# pqc-rev3.net
KiCad netlist of a schematic drawn in EAGLE
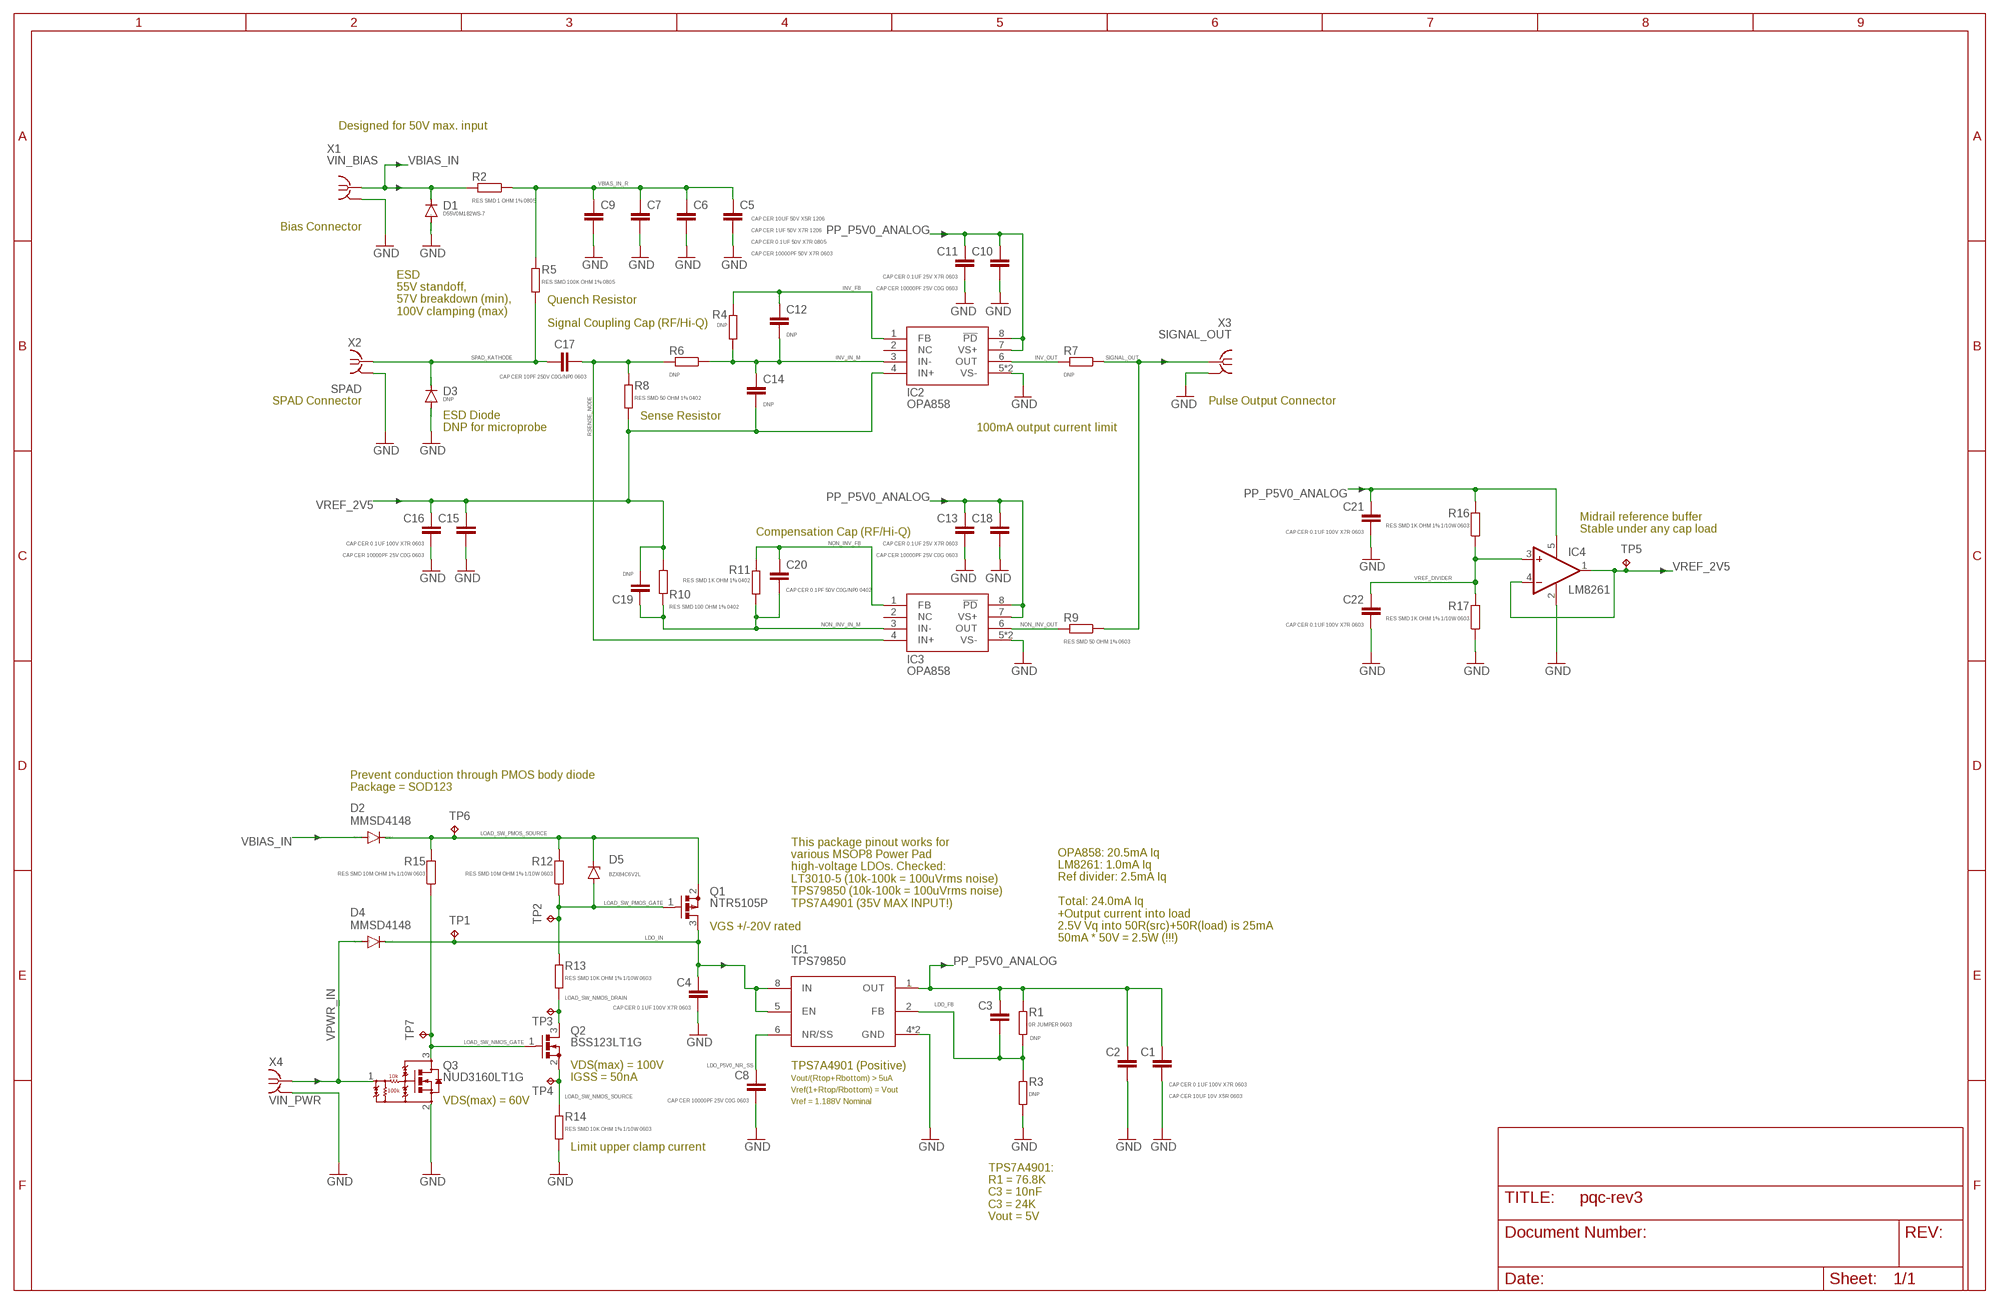
[diagram p0: schematic, sheet 1]

(export (version "E")
  (design (tool "Eeschema 10.0.6"))
  (components
    (comp (ref "C1")
      (value "CAP CER 10UF 10V X5R 0603")
      (footprint "eagle-import:C0603")
      (libsource (lib "eagle-import") (part "rcl-modified-footprints_C-EUC0603"))
    )
    (comp (ref "C2")
      (value "CAP CER 0.1UF 100V X7R 0603")
      (footprint "eagle-import:C0603")
      (libsource (lib "eagle-import") (part "rcl-modified-footprints_C-EUC0603"))
    )
    (comp (ref "C3")
      (value "DNP")
      (footprint "eagle-import:C0603")
      (libsource (lib "eagle-import") (part "rcl-modified-footprints_C-EUC0603"))
    )
    (comp (ref "C4")
      (value "CAP CER 0.1UF 100V X7R 0603")
      (footprint "eagle-import:C0603")
      (libsource (lib "eagle-import") (part "rcl-modified-footprints_C-EUC0603"))
    )
    (comp (ref "C5")
      (value "CAP CER 10UF 50V X5R 1206")
      (footprint "eagle-import:C1206")
      (libsource (lib "eagle-import") (part "C-EUC1206"))
    )
    (comp (ref "C6")
      (value "CAP CER 1UF 50V X7R 1206")
      (footprint "eagle-import:C1206")
      (libsource (lib "eagle-import") (part "C-EUC1206"))
    )
    (comp (ref "C7")
      (value "CAP CER 0.1UF 50V X7R 0805")
      (footprint "eagle-import:C0805")
      (libsource (lib "eagle-import") (part "C-EUC0805"))
    )
    (comp (ref "C8")
      (value "CAP CER 10000PF 25V C0G 0603")
      (footprint "eagle-import:C0603")
      (libsource (lib "eagle-import") (part "rcl-modified-footprints_C-EUC0603"))
    )
    (comp (ref "C9")
      (value "CAP CER 10000PF 50V X7R 0603")
      (footprint "eagle-import:C0603")
      (libsource (lib "eagle-import") (part "rcl-modified-footprints_C-EUC0603"))
    )
    (comp (ref "C10")
      (value "CAP CER 10000PF 25V C0G 0603")
      (footprint "eagle-import:C0603")
      (libsource (lib "eagle-import") (part "rcl-modified-footprints_C-EUC0603"))
    )
    (comp (ref "C11")
      (value "CAP CER 0.1UF 25V X7R 0603")
      (footprint "eagle-import:C0603")
      (libsource (lib "eagle-import") (part "rcl-modified-footprints_C-EUC0603"))
    )
    (comp (ref "C12")
      (value "DNP")
      (footprint "eagle-import:C0402")
      (libsource (lib "eagle-import") (part "rcl-modified-footprints_C-EUC0402"))
    )
    (comp (ref "C13")
      (value "CAP CER 0.1UF 25V X7R 0603")
      (footprint "eagle-import:C0603")
      (libsource (lib "eagle-import") (part "rcl-modified-footprints_C-EUC0603"))
    )
    (comp (ref "C14")
      (value "DNP")
      (footprint "eagle-import:C0402")
      (libsource (lib "eagle-import") (part "rcl-modified-footprints_C-EUC0402"))
    )
    (comp (ref "C15")
      (value "CAP CER 10000PF 25V C0G 0603")
      (footprint "eagle-import:C0603")
      (libsource (lib "eagle-import") (part "rcl-modified-footprints_C-EUC0603"))
    )
    (comp (ref "C16")
      (value "CAP CER 0.1UF 100V X7R 0603")
      (footprint "eagle-import:C0603")
      (libsource (lib "eagle-import") (part "rcl-modified-footprints_C-EUC0603"))
    )
    (comp (ref "C17")
      (value "CAP CER 10PF 250V C0G/NP0 0603")
      (footprint "eagle-import:C0603")
      (libsource (lib "eagle-import") (part "rcl-modified-footprints_C-EUC0603"))
    )
    (comp (ref "C18")
      (value "CAP CER 10000PF 25V C0G 0603")
      (footprint "eagle-import:C0603")
      (libsource (lib "eagle-import") (part "rcl-modified-footprints_C-EUC0603"))
    )
    (comp (ref "C19")
      (value "DNP")
      (footprint "eagle-import:C0402")
      (libsource (lib "eagle-import") (part "rcl-modified-footprints_C-EUC0402"))
    )
    (comp (ref "C20")
      (value "CAP CER 0.1PF 50V C0G/NP0 0402")
      (footprint "eagle-import:C0402")
      (libsource (lib "eagle-import") (part "rcl-modified-footprints_C-EUC0402"))
    )
    (comp (ref "C21")
      (value "CAP CER 0.1UF 100V X7R 0603")
      (footprint "eagle-import:C0603")
      (libsource (lib "eagle-import") (part "rcl-modified-footprints_C-EUC0603"))
    )
    (comp (ref "C22")
      (value "CAP CER 0.1UF 100V X7R 0603")
      (footprint "eagle-import:C0603")
      (libsource (lib "eagle-import") (part "rcl-modified-footprints_C-EUC0603"))
    )
    (comp (ref "D1")
      (value "D55V0M1B2WS-7")
      (footprint "eagle-import:SOD323-W")
      (libsource (lib "eagle-import") (part "DIODE-SOD323-W"))
    )
    (comp (ref "D2")
      (value "MMSD4148")
      (footprint "eagle-import:SOD123")
      (libsource (lib "eagle-import") (part "DIODE-SOD123"))
    )
    (comp (ref "D3")
      (value "DNP")
      (footprint "eagle-import:SOD323-W")
      (libsource (lib "eagle-import") (part "DIODE-SOD323-W"))
    )
    (comp (ref "D4")
      (value "MMSD4148")
      (footprint "eagle-import:SOD123")
      (libsource (lib "eagle-import") (part "DIODE-SOD123"))
    )
    (comp (ref "D5")
      (value "BZX84C6V2L")
      (footprint "eagle-import:SOT23")
      (libsource (lib "eagle-import") (part "ZENER-DIODESOT23"))
    )
    (comp (ref "IC1")
      (value "TPS79850")
      (footprint "eagle-import:MSOP-8_POWER_PAD")
      (libsource (lib "eagle-import") (part "TPS7A"))
    )
    (comp (ref "IC2")
      (value "OPA858")
      (footprint "eagle-import:WSON8")
      (libsource (lib "eagle-import") (part "OPA858"))
    )
    (comp (ref "IC3")
      (value "OPA858")
      (footprint "eagle-import:WSON8")
      (libsource (lib "eagle-import") (part "OPA858"))
    )
    (comp (ref "IC4")
      (value "LM8261")
      (footprint "eagle-import:SOT23-5")
      (libsource (lib "eagle-import") (part "LM8261"))
    )
    (comp (ref "Q1")
      (value "NTR5105P")
      (footprint "eagle-import:SOT23C")
      (libsource (lib "eagle-import") (part "PMOS_GENERIC_SOT23-3"))
    )
    (comp (ref "Q2")
      (value "BSS123LT1G")
      (footprint "eagle-import:SOT23C")
      (libsource (lib "eagle-import") (part "NMOS_GENERIC"))
    )
    (comp (ref "Q3")
      (value "NUD3160LT1G")
      (footprint "eagle-import:SOT23C")
      (libsource (lib "eagle-import") (part "NUD3160LT1G"))
    )
    (comp (ref "R1")
      (value "0R JUMPER 0603")
      (footprint "eagle-import:R0603")
      (libsource (lib "eagle-import") (part "R-EU_R0603"))
    )
    (comp (ref "R2")
      (value "RES SMD 1 OHM 1% 0805")
      (footprint "eagle-import:R0805")
      (libsource (lib "eagle-import") (part "rcl_334_R-EU_R0805"))
    )
    (comp (ref "R3")
      (value "DNP")
      (footprint "eagle-import:R0603")
      (libsource (lib "eagle-import") (part "R-EU_R0603"))
    )
    (comp (ref "R4")
      (value "DNP")
      (footprint "eagle-import:R0402")
      (libsource (lib "eagle-import") (part "R-EU_R0402"))
    )
    (comp (ref "R5")
      (value "RES SMD 100K OHM 1% 0805")
      (footprint "eagle-import:R0805")
      (libsource (lib "eagle-import") (part "rcl_334_R-EU_R0805"))
    )
    (comp (ref "R6")
      (value "DNP")
      (footprint "eagle-import:R0402")
      (libsource (lib "eagle-import") (part "R-EU_R0402"))
    )
    (comp (ref "R7")
      (value "DNP")
      (footprint "eagle-import:R0603")
      (libsource (lib "eagle-import") (part "R-EU_R0603"))
    )
    (comp (ref "R8")
      (value "RES SMD 50 OHM 1% 0402")
      (footprint "eagle-import:R0402")
      (libsource (lib "eagle-import") (part "R-EU_R0402"))
    )
    (comp (ref "R9")
      (value "RES SMD 50 OHM 1% 0603")
      (footprint "eagle-import:R0603")
      (libsource (lib "eagle-import") (part "R-EU_R0603"))
    )
    (comp (ref "R10")
      (value "RES SMD 100 OHM 1% 0402")
      (footprint "eagle-import:R0402")
      (libsource (lib "eagle-import") (part "R-EU_R0402"))
    )
    (comp (ref "R11")
      (value "RES SMD 1K OHM 1% 0402")
      (footprint "eagle-import:R0402")
      (libsource (lib "eagle-import") (part "R-EU_R0402"))
    )
    (comp (ref "R12")
      (value "RES SMD 10M OHM 1% 1/10W 0603")
      (footprint "eagle-import:R0603")
      (libsource (lib "eagle-import") (part "R-EU_R0603"))
    )
    (comp (ref "R13")
      (value "RES SMD 10K OHM 1% 1/10W 0603")
      (footprint "eagle-import:R0603")
      (libsource (lib "eagle-import") (part "R-EU_R0603"))
    )
    (comp (ref "R14")
      (value "RES SMD 10K OHM 1% 1/10W 0603")
      (footprint "eagle-import:R0603")
      (libsource (lib "eagle-import") (part "R-EU_R0603"))
    )
    (comp (ref "R15")
      (value "RES SMD 10M OHM 1% 1/10W 0603")
      (footprint "eagle-import:R0603")
      (libsource (lib "eagle-import") (part "R-EU_R0603"))
    )
    (comp (ref "R16")
      (value "RES SMD 1K OHM 1% 1/10W 0603")
      (footprint "eagle-import:R0603")
      (libsource (lib "eagle-import") (part "R-EU_R0603"))
    )
    (comp (ref "R17")
      (value "RES SMD 1K OHM 1% 1/10W 0603")
      (footprint "eagle-import:R0603")
      (libsource (lib "eagle-import") (part "R-EU_R0603"))
    )
    (comp (ref "TP1")
      (value "TPTP10R")
      (footprint "eagle-import:TP10R")
      (libsource (lib "eagle-import") (part "TPTP10R"))
    )
    (comp (ref "TP2")
      (value "TPTP10R")
      (footprint "eagle-import:TP10R")
      (libsource (lib "eagle-import") (part "TPTP10R"))
    )
    (comp (ref "TP3")
      (value "TPTP10R")
      (footprint "eagle-import:TP10R")
      (libsource (lib "eagle-import") (part "TPTP10R"))
    )
    (comp (ref "TP4")
      (value "TPTP10R")
      (footprint "eagle-import:TP10R")
      (libsource (lib "eagle-import") (part "TPTP10R"))
    )
    (comp (ref "TP5")
      (value "TPTP10R")
      (footprint "eagle-import:TP10R")
      (libsource (lib "eagle-import") (part "TPTP10R"))
    )
    (comp (ref "TP6")
      (value "TPTP10R")
      (footprint "eagle-import:TP10R")
      (libsource (lib "eagle-import") (part "TPTP10R"))
    )
    (comp (ref "TP7")
      (value "TPB1,27")
      (footprint "eagle-import:B1,27")
      (libsource (lib "eagle-import") (part "TPB1,27"))
    )
    (comp (ref "X1")
      (value "VIN_BIAS")
      (footprint "eagle-import:MMCX-J-P-X-ST-EM1-MKT")
      (fields (field (name "MF") "Samtec Inc.") (field (name "MPN") "MMCX-J-P-X-ST-EM1-MKT"))
      (libsource (lib "eagle-import") (part "COAX"))
    )
    (comp (ref "X2")
      (value "SPAD")
      (footprint "eagle-import:J502-ND-142-0701-881_886")
      (fields (field (name "MF") "JOHNSON COMPONENTS") (field (name "MPN") "142-0701-881"))
      (libsource (lib "eagle-import") (part "SMA-142-0701-881/886"))
    )
    (comp (ref "X3")
      (value "SIGNAL_OUT")
      (footprint "eagle-import:MMCX-J-P-X-ST-EM1-MKT")
      (fields (field (name "MF") "Samtec Inc.") (field (name "MPN") "MMCX-J-P-X-ST-EM1-MKT"))
      (libsource (lib "eagle-import") (part "COAX"))
    )
    (comp (ref "X4")
      (value "VIN_PWR")
      (footprint "eagle-import:MMCX-J-P-X-ST-EM1-MKT")
      (fields (field (name "MF") "Samtec Inc.") (field (name "MPN") "MMCX-J-P-X-ST-EM1-MKT"))
      (libsource (lib "eagle-import") (part "COAX"))
    )
  )
  (nets
    (net (code "1") (name "/INV_FB") (class "Default")
      (node (ref "C12") (pin "1") (pinfunction "1_1") (pintype "passive"))
      (node (ref "IC2") (pin "1") (pinfunction "FB_1") (pintype "bidirectional"))
      (node (ref "R4") (pin "1") (pinfunction "1_1") (pintype "passive"))
    )
    (net (code "2") (name "/INV_IN_M") (class "Default")
      (node (ref "C12") (pin "2") (pinfunction "2_2") (pintype "passive"))
      (node (ref "C14") (pin "1") (pinfunction "1_1") (pintype "passive"))
      (node (ref "IC2") (pin "3") (pinfunction "IN-_3") (pintype "bidirectional"))
      (node (ref "R4") (pin "2") (pinfunction "2_2") (pintype "passive"))
      (node (ref "R6") (pin "1") (pinfunction "1_1") (pintype "passive"))
    )
    (net (code "3") (name "/INV_OUT") (class "Default")
      (node (ref "IC2") (pin "6") (pinfunction "OUT_6") (pintype "bidirectional"))
      (node (ref "R7") (pin "2") (pinfunction "2_2") (pintype "passive"))
    )
    (net (code "4") (name "/LDO_FB") (class "Default")
      (node (ref "C3") (pin "2") (pinfunction "2_2") (pintype "passive"))
      (node (ref "IC1") (pin "2") (pinfunction "FB_2") (pintype "bidirectional"))
      (node (ref "R1") (pin "1") (pinfunction "1_1") (pintype "passive"))
      (node (ref "R3") (pin "1") (pinfunction "1_1") (pintype "passive"))
    )
    (net (code "5") (name "/LDO_IN") (class "Default")
      (node (ref "C4") (pin "1") (pinfunction "1_1") (pintype "passive"))
      (node (ref "D4") (pin "C") (pinfunction "C_C") (pintype "passive"))
      (node (ref "IC1") (pin "5") (pinfunction "EN_5") (pintype "bidirectional"))
      (node (ref "IC1") (pin "8") (pinfunction "IN_8") (pintype "bidirectional"))
      (node (ref "Q1") (pin "3") (pinfunction "D_3") (pintype "passive"))
      (node (ref "TP1") (pin "TP") (pinfunction "TP_TP") (pintype "input"))
    )
    (net (code "6") (name "/LDO_P5V0_NR_SS") (class "Default")
      (node (ref "C8") (pin "1") (pinfunction "1_1") (pintype "passive"))
      (node (ref "IC1") (pin "6") (pinfunction "NR/SS_6") (pintype "bidirectional"))
    )
    (net (code "7") (name "/LOAD_SW_NMOS_DRAIN") (class "Default")
      (node (ref "Q2") (pin "3") (pinfunction "D_3") (pintype "passive"))
      (node (ref "R13") (pin "1") (pinfunction "1_1") (pintype "passive"))
      (node (ref "TP3") (pin "TP") (pinfunction "TP_TP") (pintype "input"))
    )
    (net (code "8") (name "/LOAD_SW_NMOS_GATE") (class "Default")
      (node (ref "Q2") (pin "1") (pinfunction "G_1") (pintype "passive"))
      (node (ref "Q3") (pin "3") (pinfunction "D_3") (pintype "passive"))
      (node (ref "R15") (pin "1") (pinfunction "1_1") (pintype "passive"))
      (node (ref "TP7") (pin "TP") (pinfunction "TP_TP") (pintype "input"))
    )
    (net (code "9") (name "/LOAD_SW_NMOS_SOURCE") (class "Default")
      (node (ref "Q2") (pin "2") (pinfunction "S_2") (pintype "passive"))
      (node (ref "R14") (pin "2") (pinfunction "2_2") (pintype "passive"))
      (node (ref "TP4") (pin "TP") (pinfunction "TP_TP") (pintype "input"))
    )
    (net (code "10") (name "/LOAD_SW_PMOS_GATE") (class "Default")
      (node (ref "D5") (pin "1") (pinfunction "A_1") (pintype "passive"))
      (node (ref "Q1") (pin "1") (pinfunction "G_1") (pintype "passive"))
      (node (ref "R12") (pin "1") (pinfunction "1_1") (pintype "passive"))
      (node (ref "R13") (pin "2") (pinfunction "2_2") (pintype "passive"))
      (node (ref "TP2") (pin "TP") (pinfunction "TP_TP") (pintype "input"))
    )
    (net (code "11") (name "/LOAD_SW_PMOS_SOURCE") (class "Default")
      (node (ref "D2") (pin "C") (pinfunction "C_C") (pintype "passive"))
      (node (ref "D5") (pin "3") (pinfunction "C_3") (pintype "passive"))
      (node (ref "Q1") (pin "2") (pinfunction "S_2") (pintype "passive"))
      (node (ref "R12") (pin "2") (pinfunction "2_2") (pintype "passive"))
      (node (ref "R15") (pin "2") (pinfunction "2_2") (pintype "passive"))
      (node (ref "TP6") (pin "TP") (pinfunction "TP_TP") (pintype "input"))
    )
    (net (code "12") (name "/NON_INV_FB") (class "Default")
      (node (ref "C20") (pin "1") (pinfunction "1_1") (pintype "passive"))
      (node (ref "IC3") (pin "1") (pinfunction "FB_1") (pintype "bidirectional"))
      (node (ref "R11") (pin "1") (pinfunction "1_1") (pintype "passive"))
    )
    (net (code "13") (name "/NON_INV_IN_M") (class "Default")
      (node (ref "C19") (pin "1") (pinfunction "1_1") (pintype "passive"))
      (node (ref "C20") (pin "2") (pinfunction "2_2") (pintype "passive"))
      (node (ref "IC3") (pin "3") (pinfunction "IN-_3") (pintype "bidirectional"))
      (node (ref "R10") (pin "1") (pinfunction "1_1") (pintype "passive"))
      (node (ref "R11") (pin "2") (pinfunction "2_2") (pintype "passive"))
    )
    (net (code "14") (name "/NON_INV_OUT") (class "Default")
      (node (ref "IC3") (pin "6") (pinfunction "OUT_6") (pintype "bidirectional"))
      (node (ref "R9") (pin "2") (pinfunction "2_2") (pintype "passive"))
    )
    (net (code "15") (name "/PP_P5V0_ANALOG") (class "Default")
      (node (ref "C1") (pin "1") (pinfunction "1_1") (pintype "passive"))
      (node (ref "C10") (pin "1") (pinfunction "1_1") (pintype "passive"))
      (node (ref "C11") (pin "1") (pinfunction "1_1") (pintype "passive"))
      (node (ref "C13") (pin "1") (pinfunction "1_1") (pintype "passive"))
      (node (ref "C18") (pin "1") (pinfunction "1_1") (pintype "passive"))
      (node (ref "C2") (pin "1") (pinfunction "1_1") (pintype "passive"))
      (node (ref "C21") (pin "1") (pinfunction "1_1") (pintype "passive"))
      (node (ref "C3") (pin "1") (pinfunction "1_1") (pintype "passive"))
      (node (ref "IC1") (pin "1") (pinfunction "OUT_1") (pintype "bidirectional"))
      (node (ref "IC2") (pin "7") (pinfunction "VS+_7") (pintype "bidirectional"))
      (node (ref "IC2") (pin "8") (pinfunction "~{PD}_8") (pintype "bidirectional"))
      (node (ref "IC3") (pin "7") (pinfunction "VS+_7") (pintype "bidirectional"))
      (node (ref "IC3") (pin "8") (pinfunction "~{PD}_8") (pintype "bidirectional"))
      (node (ref "IC4") (pin "5") (pinfunction "V+_5") (pintype "power_in"))
      (node (ref "R1") (pin "2") (pinfunction "2_2") (pintype "passive"))
      (node (ref "R16") (pin "2") (pinfunction "2_2") (pintype "passive"))
    )
    (net (code "16") (name "/RSENSE_NODE") (class "Default")
      (node (ref "C17") (pin "2") (pinfunction "2_2") (pintype "passive"))
      (node (ref "IC3") (pin "4") (pinfunction "IN+_4") (pintype "bidirectional"))
      (node (ref "R6") (pin "2") (pinfunction "2_2") (pintype "passive"))
      (node (ref "R8") (pin "2") (pinfunction "2_2") (pintype "passive"))
    )
    (net (code "17") (name "/SIGNAL_OUT") (class "Default")
      (node (ref "R7") (pin "1") (pinfunction "1_1") (pintype "passive"))
      (node (ref "R9") (pin "1") (pinfunction "1_1") (pintype "passive"))
      (node (ref "X3") (pin "1") (pinfunction "1_1") (pintype "passive"))
    )
    (net (code "18") (name "/SPAD_KATHODE") (class "Default")
      (node (ref "C17") (pin "1") (pinfunction "1_1") (pintype "passive"))
      (node (ref "D3") (pin "C") (pinfunction "C_C") (pintype "passive"))
      (node (ref "R5") (pin "1") (pinfunction "1_1") (pintype "passive"))
      (node (ref "X2") (pin "1") (pinfunction "1_1") (pintype "passive"))
    )
    (net (code "19") (name "/VBIAS_IN") (class "Default")
      (node (ref "D1") (pin "C") (pinfunction "C_C") (pintype "passive"))
      (node (ref "D2") (pin "A") (pinfunction "A_A") (pintype "passive"))
      (node (ref "R2") (pin "2") (pinfunction "2_2") (pintype "passive"))
      (node (ref "X1") (pin "1") (pinfunction "1_1") (pintype "passive"))
    )
    (net (code "20") (name "/VBIAS_IN_R") (class "Default")
      (node (ref "C5") (pin "1") (pinfunction "1_1") (pintype "passive"))
      (node (ref "C6") (pin "1") (pinfunction "1_1") (pintype "passive"))
      (node (ref "C7") (pin "1") (pinfunction "1_1") (pintype "passive"))
      (node (ref "C9") (pin "1") (pinfunction "1_1") (pintype "passive"))
      (node (ref "R2") (pin "1") (pinfunction "1_1") (pintype "passive"))
      (node (ref "R5") (pin "2") (pinfunction "2_2") (pintype "passive"))
    )
    (net (code "21") (name "/VPWR_IN") (class "Default")
      (node (ref "D4") (pin "A") (pinfunction "A_A") (pintype "passive"))
      (node (ref "Q3") (pin "1") (pinfunction "G_1") (pintype "passive"))
      (node (ref "X4") (pin "1") (pinfunction "1_1") (pintype "passive"))
    )
    (net (code "22") (name "/VREF_2V5") (class "Default")
      (node (ref "C14") (pin "2") (pinfunction "2_2") (pintype "passive"))
      (node (ref "C15") (pin "1") (pinfunction "1_1") (pintype "passive"))
      (node (ref "C16") (pin "1") (pinfunction "1_1") (pintype "passive"))
      (node (ref "C19") (pin "2") (pinfunction "2_2") (pintype "passive"))
      (node (ref "IC2") (pin "4") (pinfunction "IN+_4") (pintype "bidirectional"))
      (node (ref "IC4") (pin "1") (pinfunction "OUT_1") (pintype "output"))
      (node (ref "IC4") (pin "4") (pinfunction "-IN_4") (pintype "input"))
      (node (ref "R10") (pin "2") (pinfunction "2_2") (pintype "passive"))
      (node (ref "R8") (pin "1") (pinfunction "1_1") (pintype "passive"))
      (node (ref "TP5") (pin "TP") (pinfunction "TP_TP") (pintype "input"))
    )
    (net (code "23") (name "/VREF_DIVIDER") (class "Default")
      (node (ref "C22") (pin "1") (pinfunction "1_1") (pintype "passive"))
      (node (ref "IC4") (pin "3") (pinfunction "+IN_3") (pintype "input"))
      (node (ref "R16") (pin "1") (pinfunction "1_1") (pintype "passive"))
      (node (ref "R17") (pin "2") (pinfunction "2_2") (pintype "passive"))
    )
    (net (code "24") (name "GND") (class "Default")
      (node (ref "C1") (pin "2") (pinfunction "2_2") (pintype "passive"))
      (node (ref "C10") (pin "2") (pinfunction "2_2") (pintype "passive"))
      (node (ref "C11") (pin "2") (pinfunction "2_2") (pintype "passive"))
      (node (ref "C13") (pin "2") (pinfunction "2_2") (pintype "passive"))
      (node (ref "C15") (pin "2") (pinfunction "2_2") (pintype "passive"))
      (node (ref "C16") (pin "2") (pinfunction "2_2") (pintype "passive"))
      (node (ref "C18") (pin "2") (pinfunction "2_2") (pintype "passive"))
      (node (ref "C2") (pin "2") (pinfunction "2_2") (pintype "passive"))
      (node (ref "C21") (pin "2") (pinfunction "2_2") (pintype "passive"))
      (node (ref "C22") (pin "2") (pinfunction "2_2") (pintype "passive"))
      (node (ref "C4") (pin "2") (pinfunction "2_2") (pintype "passive"))
      (node (ref "C5") (pin "2") (pinfunction "2_2") (pintype "passive"))
      (node (ref "C6") (pin "2") (pinfunction "2_2") (pintype "passive"))
      (node (ref "C7") (pin "2") (pinfunction "2_2") (pintype "passive"))
      (node (ref "C8") (pin "2") (pinfunction "2_2") (pintype "passive"))
      (node (ref "C9") (pin "2") (pinfunction "2_2") (pintype "passive"))
      (node (ref "D1") (pin "A") (pinfunction "A_A") (pintype "passive"))
      (node (ref "D3") (pin "A") (pinfunction "A_A") (pintype "passive"))
      (node (ref "IC1") (pin "4") (pinfunction "GND_4") (pintype "bidirectional"))
      (node (ref "IC1") (pin "PAD") (pinfunction "GND_PAD") (pintype "bidirectional"))
      (node (ref "IC2") (pin "5") (pinfunction "VS-_5") (pintype "bidirectional"))
      (node (ref "IC2") (pin "PAD") (pinfunction "VS-_PAD") (pintype "bidirectional"))
      (node (ref "IC3") (pin "5") (pinfunction "VS-_5") (pintype "bidirectional"))
      (node (ref "IC3") (pin "PAD") (pinfunction "VS-_PAD") (pintype "bidirectional"))
      (node (ref "IC4") (pin "2") (pinfunction "V-_2") (pintype "power_in"))
      (node (ref "Q3") (pin "2") (pinfunction "S_2") (pintype "passive"))
      (node (ref "R14") (pin "1") (pinfunction "1_1") (pintype "passive"))
      (node (ref "R17") (pin "1") (pinfunction "1_1") (pintype "passive"))
      (node (ref "R3") (pin "2") (pinfunction "2_2") (pintype "passive"))
      (node (ref "X1") (pin "2@1") (pinfunction "GND_2@1") (pintype "power_in"))
      (node (ref "X2") (pin "G@1") (pinfunction "GND_G@1") (pintype "power_in"))
      (node (ref "X3") (pin "2@1") (pinfunction "GND_2@1") (pintype "power_in"))
      (node (ref "X4") (pin "2@1") (pinfunction "GND_2@1") (pintype "power_in"))
    )
    (net (code "25") (name "unconnected-(IC2-NC-Pad2)") (class "Default")
      (node (ref "IC2") (pin "2") (pinfunction "NC_2") (pintype "bidirectional"))
    )
    (net (code "26") (name "unconnected-(IC3-NC-Pad2)") (class "Default")
      (node (ref "IC3") (pin "2") (pinfunction "NC_2") (pintype "bidirectional"))
    )
  )
)
